# cn0383.net
KiCad netlist of a schematic drawn in Altium Designer
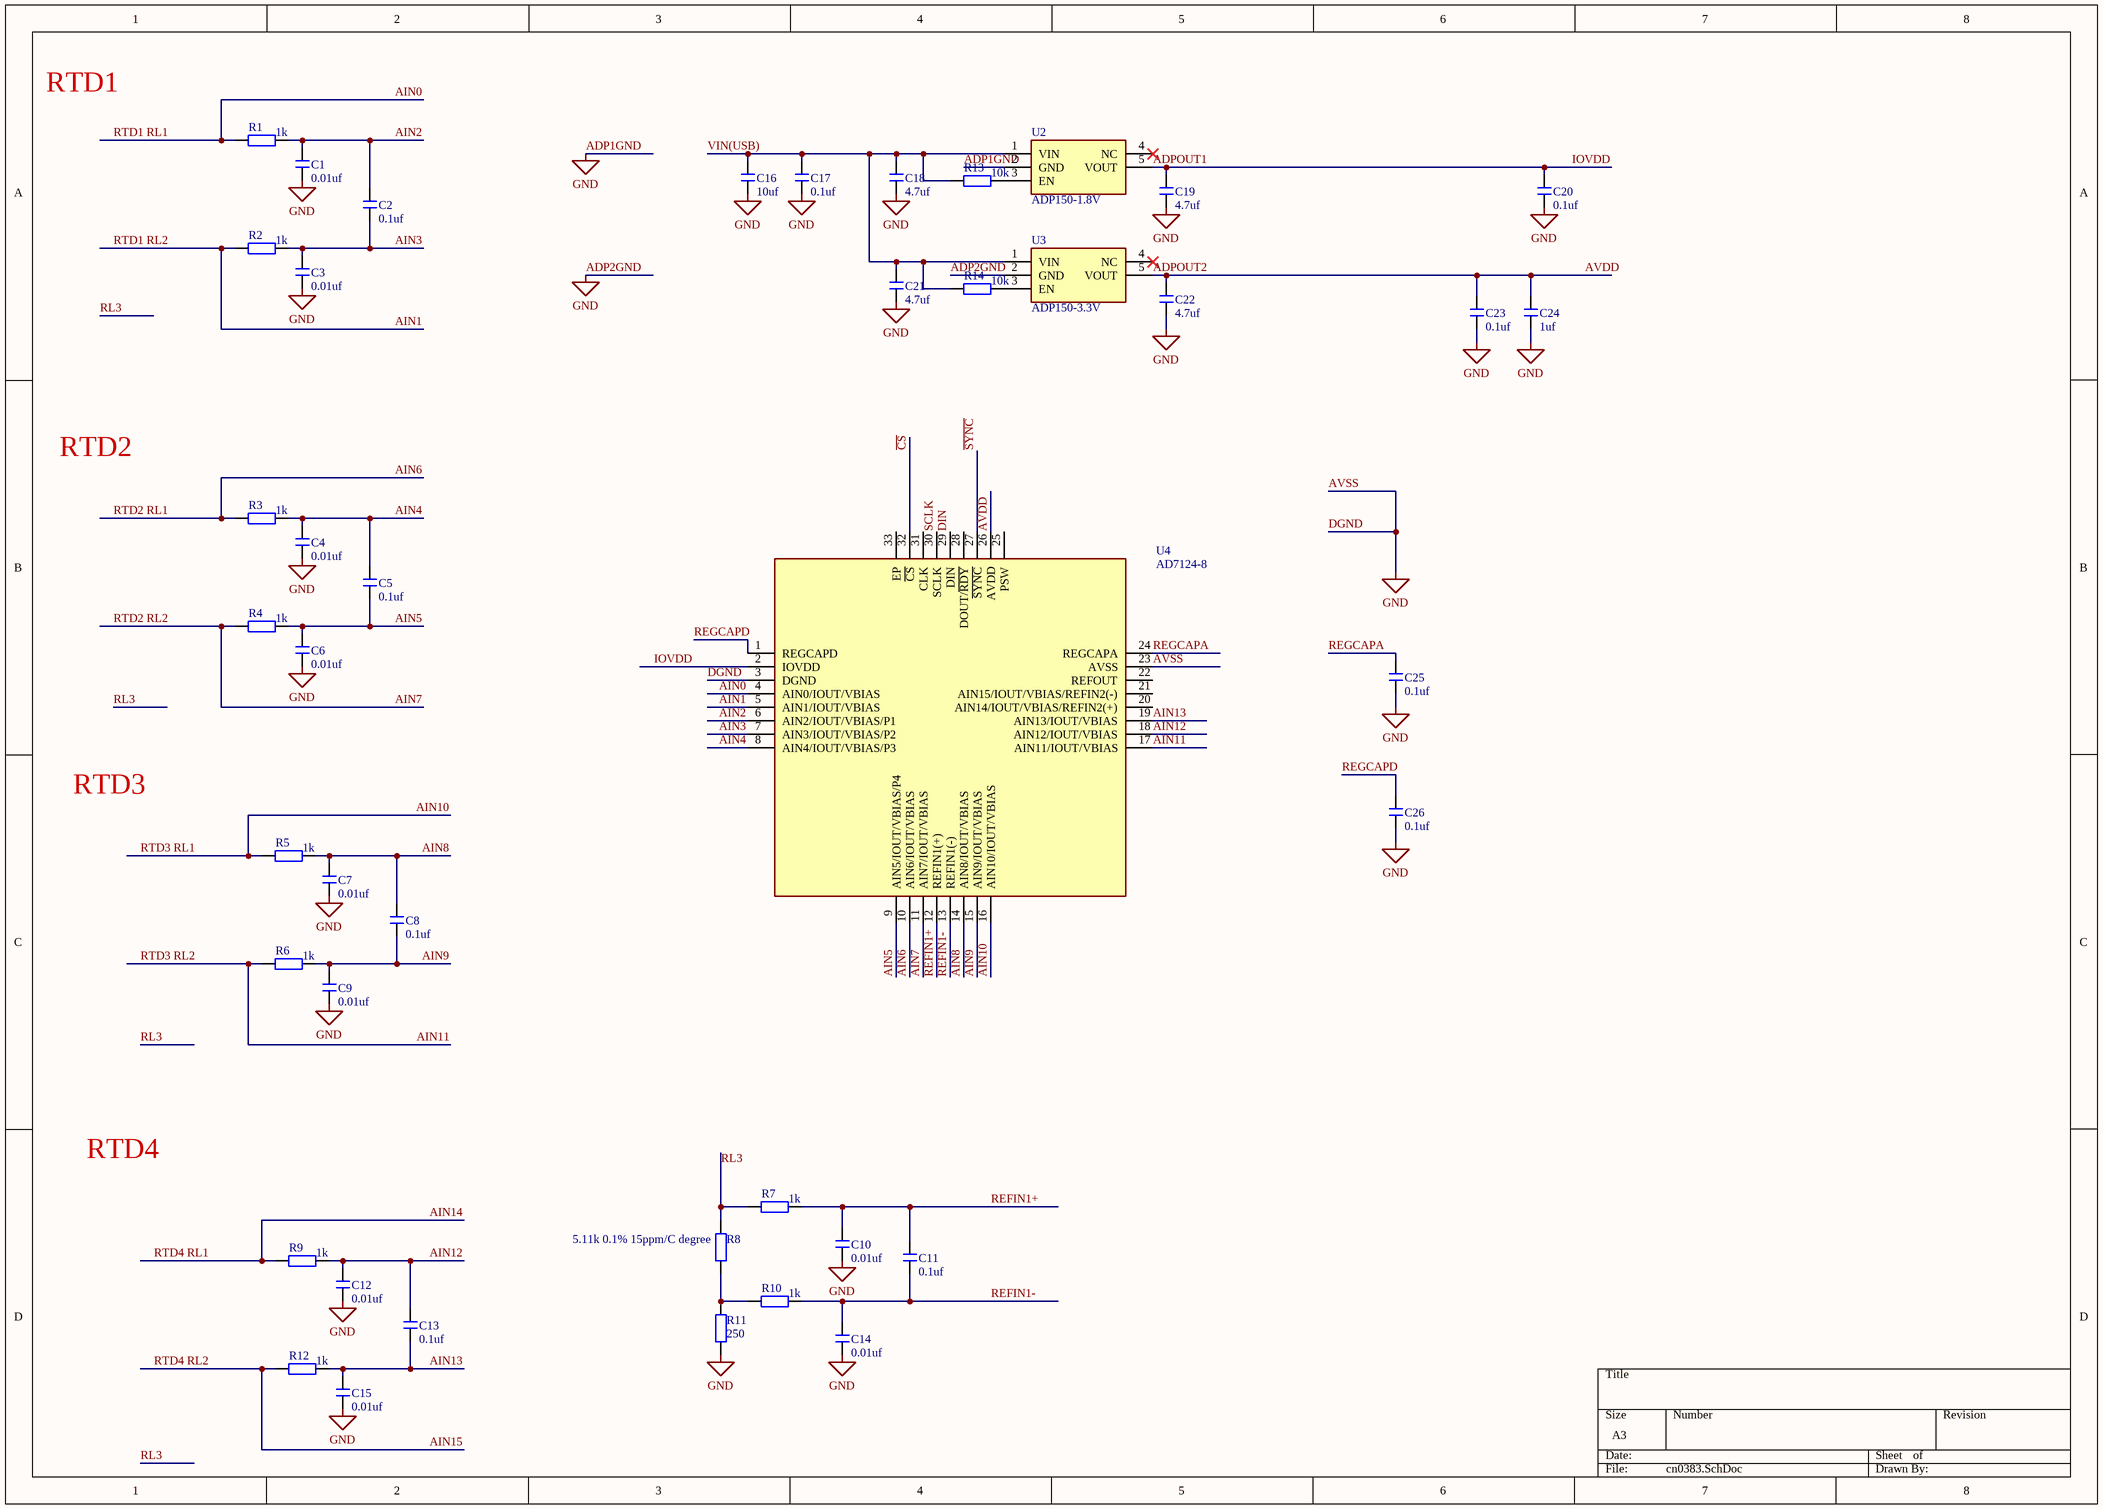
[diagram p0: cn0383.SchDoc]

(export (version "E")
  (design (tool "Eeschema 10.0.6"))
  (components
    (comp (ref "C1")
      (value "0.01uf")
      (footprint "C 0805_L")
      (description "贴片电容")
      (libsource (lib "0.1 - 电阻-电容-电感") (part "C"))
    )
    (comp (ref "C2")
      (value "0.1uf")
      (footprint "C 0805_L")
      (description "贴片电容")
      (libsource (lib "0.1 - 电阻-电容-电感") (part "C"))
    )
    (comp (ref "C3")
      (value "0.01uf")
      (footprint "C 0805_L")
      (description "贴片电容")
      (libsource (lib "0.1 - 电阻-电容-电感") (part "C"))
    )
    (comp (ref "C4")
      (value "0.01uf")
      (footprint "C 0805_L")
      (description "贴片电容")
      (libsource (lib "0.1 - 电阻-电容-电感") (part "C"))
    )
    (comp (ref "C5")
      (value "0.1uf")
      (footprint "C 0805_L")
      (description "贴片电容")
      (libsource (lib "0.1 - 电阻-电容-电感") (part "C"))
    )
    (comp (ref "C6")
      (value "0.01uf")
      (footprint "C 0805_L")
      (description "贴片电容")
      (libsource (lib "0.1 - 电阻-电容-电感") (part "C"))
    )
    (comp (ref "C7")
      (value "0.01uf")
      (footprint "C 0805_L")
      (description "贴片电容")
      (libsource (lib "0.1 - 电阻-电容-电感") (part "C"))
    )
    (comp (ref "C8")
      (value "0.1uf")
      (footprint "C 0805_L")
      (description "贴片电容")
      (libsource (lib "0.1 - 电阻-电容-电感") (part "C"))
    )
    (comp (ref "C9")
      (value "0.01uf")
      (footprint "C 0805_L")
      (description "贴片电容")
      (libsource (lib "0.1 - 电阻-电容-电感") (part "C"))
    )
    (comp (ref "C10")
      (value "0.01uf")
      (footprint "C 0805_L")
      (description "贴片电容")
      (libsource (lib "0.1 - 电阻-电容-电感") (part "C"))
    )
    (comp (ref "C11")
      (value "0.1uf")
      (footprint "C 0805_L")
      (description "贴片电容")
      (libsource (lib "0.1 - 电阻-电容-电感") (part "C"))
    )
    (comp (ref "C12")
      (value "0.01uf")
      (footprint "C 0805_L")
      (description "贴片电容")
      (libsource (lib "0.1 - 电阻-电容-电感") (part "C"))
    )
    (comp (ref "C13")
      (value "0.1uf")
      (footprint "C 0805_L")
      (description "贴片电容")
      (libsource (lib "0.1 - 电阻-电容-电感") (part "C"))
    )
    (comp (ref "C14")
      (value "0.01uf")
      (footprint "C 0805_L")
      (description "贴片电容")
      (libsource (lib "0.1 - 电阻-电容-电感") (part "C"))
    )
    (comp (ref "C15")
      (value "0.01uf")
      (footprint "C 0805_L")
      (description "贴片电容")
      (libsource (lib "0.1 - 电阻-电容-电感") (part "C"))
    )
    (comp (ref "C16")
      (value "10uf")
      (footprint "C 0805_L")
      (description "贴片电容")
      (libsource (lib "0.1 - 电阻-电容-电感") (part "C"))
    )
    (comp (ref "C17")
      (value "0.1uf")
      (footprint "C 0805_L")
      (description "贴片电容")
      (libsource (lib "0.1 - 电阻-电容-电感") (part "C"))
    )
    (comp (ref "C18")
      (value "4.7uf")
      (footprint "C 0805_L")
      (description "贴片电容")
      (libsource (lib "0.1 - 电阻-电容-电感") (part "C"))
    )
    (comp (ref "C19")
      (value "4.7uf")
      (footprint "C 0805_L")
      (description "贴片电容")
      (libsource (lib "0.1 - 电阻-电容-电感") (part "C"))
    )
    (comp (ref "C20")
      (value "0.1uf")
      (footprint "C 0805_L")
      (description "贴片电容")
      (libsource (lib "0.1 - 电阻-电容-电感") (part "C"))
    )
    (comp (ref "C21")
      (value "4.7uf")
      (footprint "C 0805_L")
      (description "贴片电容")
      (libsource (lib "0.1 - 电阻-电容-电感") (part "C"))
    )
    (comp (ref "C22")
      (value "4.7uf")
      (footprint "C 0805_L")
      (description "贴片电容")
      (libsource (lib "0.1 - 电阻-电容-电感") (part "C"))
    )
    (comp (ref "C23")
      (value "0.1uf")
      (footprint "C 0805_L")
      (description "贴片电容")
      (libsource (lib "0.1 - 电阻-电容-电感") (part "C"))
    )
    (comp (ref "C24")
      (value "1uf")
      (footprint "C 0805_L")
      (description "贴片电容")
      (libsource (lib "0.1 - 电阻-电容-电感") (part "C"))
    )
    (comp (ref "C25")
      (value "0.1uf")
      (footprint "C 0805_L")
      (description "贴片电容")
      (libsource (lib "0.1 - 电阻-电容-电感") (part "C"))
    )
    (comp (ref "C26")
      (value "0.1uf")
      (footprint "C 0805_L")
      (description "贴片电容")
      (libsource (lib "0.1 - 电阻-电容-电感") (part "C"))
    )
    (comp (ref "R1")
      (value "1k")
      (footprint "0805_R")
      (description "贴片电阻 0805 电阻")
      (libsource (lib "") (part "0805 电阻_1"))
    )
    (comp (ref "R2")
      (value "1k")
      (footprint "0805_R")
      (description "贴片电阻 0805 电阻")
      (libsource (lib "") (part "0805 电阻_1"))
    )
    (comp (ref "R3")
      (value "1k")
      (footprint "0805_R")
      (description "贴片电阻 0805 电阻")
      (libsource (lib "") (part "0805 电阻_1"))
    )
    (comp (ref "R4")
      (value "1k")
      (footprint "0805_R")
      (description "贴片电阻 0805 电阻")
      (libsource (lib "") (part "0805 电阻_1"))
    )
    (comp (ref "R5")
      (value "1k")
      (footprint "0805_R")
      (description "贴片电阻 0805 电阻")
      (libsource (lib "") (part "0805 电阻_1"))
    )
    (comp (ref "R6")
      (value "1k")
      (footprint "0805_R")
      (description "贴片电阻 0805 电阻")
      (libsource (lib "") (part "0805 电阻_1"))
    )
    (comp (ref "R7")
      (value "1k")
      (footprint "0805_R")
      (description "贴片电阻 0805 电阻")
      (libsource (lib "") (part "0805 电阻_1"))
    )
    (comp (ref "R8")
      (value "5.11k 0.1% 15ppm/C degree")
      (footprint "0805_R")
      (description "贴片电阻 0805 电阻")
      (libsource (lib "逍遥封装库") (part "0805 电阻"))
    )
    (comp (ref "R9")
      (value "1k")
      (footprint "0805_R")
      (description "贴片电阻 0805 电阻")
      (libsource (lib "") (part "0805 电阻_1"))
    )
    (comp (ref "R10")
      (value "1k")
      (footprint "0805_R")
      (description "贴片电阻 0805 电阻")
      (libsource (lib "") (part "0805 电阻_1"))
    )
    (comp (ref "R11")
      (value "250")
      (footprint "0805_R")
      (description "Reference buffer Headroom 贴片电阻 0805 电阻")
      (libsource (lib "逍遥封装库") (part "0805 电阻"))
    )
    (comp (ref "R12")
      (value "1k")
      (footprint "0805_R")
      (description "贴片电阻 0805 电阻")
      (libsource (lib "") (part "0805 电阻_1"))
    )
    (comp (ref "R13")
      (value "10k")
      (footprint "0805_R")
      (description "贴片电阻 0805 电阻")
      (libsource (lib "") (part "0805 电阻_1"))
    )
    (comp (ref "R14")
      (value "10k")
      (footprint "0805_R")
      (description "贴片电阻 0805 电阻")
      (libsource (lib "") (part "0805 电阻_1"))
    )
    (comp (ref "U2")
      (value "ADP150-1.8V")
      (description "IOVDD needs 1.8V")
      (libsource (lib "CN0383") (part "ADP150"))
    )
    (comp (ref "U3")
      (value "ADP150-3.3V")
      (description "ACDD needs 3.3V")
      (libsource (lib "CN0383") (part "ADP150"))
    )
    (comp (ref "U4") (value "AD7124-8") (libsource (lib "CN0383") (part "AD7124-8")))
  )
  (nets
    (net (code "1") (name "/ADPOUT1") (class "Default")
      (node (ref "C19") (pin "2") (pinfunction "2_2") (pintype "passive"))
      (node (ref "C20") (pin "2") (pinfunction "2_2") (pintype "passive"))
      (node (ref "U2") (pin "5") (pinfunction "VOUT_5") (pintype "passive"))
      (node (ref "U4") (pin "2") (pinfunction "IOVDD_2") (pintype "passive"))
    )
    (net (code "2") (name "/ADPOUT2") (class "Default")
      (node (ref "C22") (pin "2") (pinfunction "2_2") (pintype "passive"))
      (node (ref "C23") (pin "2") (pinfunction "2_2") (pintype "passive"))
      (node (ref "C24") (pin "2") (pinfunction "2_2") (pintype "passive"))
      (node (ref "U3") (pin "5") (pinfunction "VOUT_5") (pintype "passive"))
      (node (ref "U4") (pin "26") (pinfunction "AVDD_26") (pintype "passive"))
    )
    (net (code "3") (name "/AIN0") (class "Default")
      (node (ref "R1") (pin "1") (pinfunction "1_1") (pintype "passive"))
      (node (ref "U4") (pin "4") (pinfunction "AIN0/IOUT/VBIAS_4") (pintype "passive"))
    )
    (net (code "4") (name "/AIN1") (class "Default")
      (node (ref "R2") (pin "1") (pinfunction "1_1") (pintype "passive"))
      (node (ref "U4") (pin "5") (pinfunction "AIN1/IOUT/VBIAS_5") (pintype "passive"))
    )
    (net (code "5") (name "/AIN2") (class "Default")
      (node (ref "C1") (pin "2") (pinfunction "2_2") (pintype "passive"))
      (node (ref "C2") (pin "2") (pinfunction "2_2") (pintype "passive"))
      (node (ref "R1") (pin "2") (pinfunction "2_2") (pintype "passive"))
      (node (ref "U4") (pin "6") (pinfunction "AIN2/IOUT/VBIAS/P1_6") (pintype "passive"))
    )
    (net (code "6") (name "/AIN3") (class "Default")
      (node (ref "C2") (pin "1") (pinfunction "1_1") (pintype "passive"))
      (node (ref "C3") (pin "2") (pinfunction "2_2") (pintype "passive"))
      (node (ref "R2") (pin "2") (pinfunction "2_2") (pintype "passive"))
      (node (ref "U4") (pin "7") (pinfunction "AIN3/IOUT/VBIAS/P2_7") (pintype "passive"))
    )
    (net (code "7") (name "/AIN4") (class "Default")
      (node (ref "C4") (pin "2") (pinfunction "2_2") (pintype "passive"))
      (node (ref "C5") (pin "2") (pinfunction "2_2") (pintype "passive"))
      (node (ref "R3") (pin "2") (pinfunction "2_2") (pintype "passive"))
      (node (ref "U4") (pin "8") (pinfunction "AIN4/IOUT/VBIAS/P3_8") (pintype "passive"))
    )
    (net (code "8") (name "/AIN5") (class "Default")
      (node (ref "C5") (pin "1") (pinfunction "1_1") (pintype "passive"))
      (node (ref "C6") (pin "2") (pinfunction "2_2") (pintype "passive"))
      (node (ref "R4") (pin "2") (pinfunction "2_2") (pintype "passive"))
      (node (ref "U4") (pin "9") (pinfunction "AIN5/IOUT/VBIAS/P4_9") (pintype "passive"))
    )
    (net (code "9") (name "/AIN6") (class "Default")
      (node (ref "R3") (pin "1") (pinfunction "1_1") (pintype "passive"))
      (node (ref "U4") (pin "10") (pinfunction "AIN6/IOUT/VBIAS_10") (pintype "passive"))
    )
    (net (code "10") (name "/AIN7") (class "Default")
      (node (ref "R4") (pin "1") (pinfunction "1_1") (pintype "passive"))
      (node (ref "U4") (pin "11") (pinfunction "AIN7/IOUT/VBIAS_11") (pintype "passive"))
    )
    (net (code "11") (name "/AIN8") (class "Default")
      (node (ref "C7") (pin "2") (pinfunction "2_2") (pintype "passive"))
      (node (ref "C8") (pin "2") (pinfunction "2_2") (pintype "passive"))
      (node (ref "R5") (pin "2") (pinfunction "2_2") (pintype "passive"))
      (node (ref "U4") (pin "14") (pinfunction "AIN8/IOUT/VBIAS_14") (pintype "passive"))
    )
    (net (code "12") (name "/AIN9") (class "Default")
      (node (ref "C8") (pin "1") (pinfunction "1_1") (pintype "passive"))
      (node (ref "C9") (pin "2") (pinfunction "2_2") (pintype "passive"))
      (node (ref "R6") (pin "2") (pinfunction "2_2") (pintype "passive"))
      (node (ref "U4") (pin "15") (pinfunction "AIN9/IOUT/VBIAS_15") (pintype "passive"))
    )
    (net (code "13") (name "/AIN10") (class "Default")
      (node (ref "R5") (pin "1") (pinfunction "1_1") (pintype "passive"))
      (node (ref "U4") (pin "16") (pinfunction "AIN10/IOUT/VBIAS_16") (pintype "passive"))
    )
    (net (code "14") (name "/AIN11") (class "Default")
      (node (ref "R6") (pin "1") (pinfunction "1_1") (pintype "passive"))
      (node (ref "U4") (pin "17") (pinfunction "AIN11/IOUT/VBIAS_17") (pintype "passive"))
    )
    (net (code "15") (name "/AIN12") (class "Default")
      (node (ref "C12") (pin "2") (pinfunction "2_2") (pintype "passive"))
      (node (ref "C13") (pin "2") (pinfunction "2_2") (pintype "passive"))
      (node (ref "R9") (pin "2") (pinfunction "2_2") (pintype "passive"))
      (node (ref "U4") (pin "18") (pinfunction "AIN12/IOUT/VBIAS_18") (pintype "passive"))
    )
    (net (code "16") (name "/AIN13") (class "Default")
      (node (ref "C13") (pin "1") (pinfunction "1_1") (pintype "passive"))
      (node (ref "C15") (pin "2") (pinfunction "2_2") (pintype "passive"))
      (node (ref "R12") (pin "2") (pinfunction "2_2") (pintype "passive"))
      (node (ref "U4") (pin "19") (pinfunction "AIN13/IOUT/VBIAS_19") (pintype "passive"))
    )
    (net (code "17") (name "/AIN14") (class "Default")
      (node (ref "R9") (pin "1") (pinfunction "1_1") (pintype "passive"))
    )
    (net (code "18") (name "/AIN15") (class "Default")
      (node (ref "R12") (pin "1") (pinfunction "1_1") (pintype "passive"))
    )
    (net (code "19") (name "/DIN") (class "Default")
      (node (ref "U4") (pin "29") (pinfunction "DIN_29") (pintype "passive"))
    )
    (net (code "20") (name "/REFIN1+") (class "Default")
      (node (ref "C10") (pin "2") (pinfunction "2_2") (pintype "passive"))
      (node (ref "C11") (pin "2") (pinfunction "2_2") (pintype "passive"))
      (node (ref "R7") (pin "2") (pinfunction "2_2") (pintype "passive"))
      (node (ref "U4") (pin "12") (pinfunction "REFIN1(+)_12") (pintype "passive"))
    )
    (net (code "21") (name "/REFIN1-") (class "Default")
      (node (ref "C11") (pin "1") (pinfunction "1_1") (pintype "passive"))
      (node (ref "C14") (pin "2") (pinfunction "2_2") (pintype "passive"))
      (node (ref "R10") (pin "2") (pinfunction "2_2") (pintype "passive"))
      (node (ref "U4") (pin "13") (pinfunction "REFIN1(-)_13") (pintype "passive"))
    )
    (net (code "22") (name "/REGCAPA") (class "Default")
      (node (ref "C25") (pin "2") (pinfunction "2_2") (pintype "passive"))
      (node (ref "U4") (pin "24") (pinfunction "REGCAPA_24") (pintype "passive"))
    )
    (net (code "23") (name "/REGCAPD") (class "Default")
      (node (ref "C26") (pin "2") (pinfunction "2_2") (pintype "passive"))
      (node (ref "U4") (pin "1") (pinfunction "REGCAPD_1") (pintype "passive"))
    )
    (net (code "24") (name "/RL3") (class "Default")
      (node (ref "R7") (pin "1") (pinfunction "1_1") (pintype "passive"))
      (node (ref "R8") (pin "2") (pinfunction "2_2") (pintype "passive"))
    )
    (net (code "25") (name "/SCLK") (class "Default")
      (node (ref "U4") (pin "30") (pinfunction "SCLK_30") (pintype "passive"))
    )
    (net (code "26") (name "/VIN(USB)") (class "Default")
      (node (ref "C16") (pin "2") (pinfunction "2_2") (pintype "passive"))
      (node (ref "C17") (pin "2") (pinfunction "2_2") (pintype "passive"))
      (node (ref "C18") (pin "2") (pinfunction "2_2") (pintype "passive"))
      (node (ref "C21") (pin "2") (pinfunction "2_2") (pintype "passive"))
      (node (ref "R13") (pin "1") (pinfunction "1_1") (pintype "passive"))
      (node (ref "R14") (pin "1") (pinfunction "1_1") (pintype "passive"))
      (node (ref "U2") (pin "1") (pinfunction "VIN_1") (pintype "passive"))
      (node (ref "U3") (pin "1") (pinfunction "VIN_1") (pintype "passive"))
    )
    (net (code "27") (name "/~{CS}") (class "Default")
      (node (ref "U4") (pin "32") (pinfunction "~{CS}_32") (pintype "passive"))
    )
    (net (code "28") (name "/~{SYNC}") (class "Default")
      (node (ref "U4") (pin "27") (pinfunction "~{SYNC}_27") (pintype "passive"))
    )
    (net (code "29") (name "GND") (class "Default")
      (node (ref "C1") (pin "1") (pinfunction "1_1") (pintype "passive"))
      (node (ref "C10") (pin "1") (pinfunction "1_1") (pintype "passive"))
      (node (ref "C12") (pin "1") (pinfunction "1_1") (pintype "passive"))
      (node (ref "C14") (pin "1") (pinfunction "1_1") (pintype "passive"))
      (node (ref "C15") (pin "1") (pinfunction "1_1") (pintype "passive"))
      (node (ref "C16") (pin "1") (pinfunction "1_1") (pintype "passive"))
      (node (ref "C17") (pin "1") (pinfunction "1_1") (pintype "passive"))
      (node (ref "C18") (pin "1") (pinfunction "1_1") (pintype "passive"))
      (node (ref "C19") (pin "1") (pinfunction "1_1") (pintype "passive"))
      (node (ref "C20") (pin "1") (pinfunction "1_1") (pintype "passive"))
      (node (ref "C21") (pin "1") (pinfunction "1_1") (pintype "passive"))
      (node (ref "C22") (pin "1") (pinfunction "1_1") (pintype "passive"))
      (node (ref "C23") (pin "1") (pinfunction "1_1") (pintype "passive"))
      (node (ref "C24") (pin "1") (pinfunction "1_1") (pintype "passive"))
      (node (ref "C25") (pin "1") (pinfunction "1_1") (pintype "passive"))
      (node (ref "C26") (pin "1") (pinfunction "1_1") (pintype "passive"))
      (node (ref "C3") (pin "1") (pinfunction "1_1") (pintype "passive"))
      (node (ref "C4") (pin "1") (pinfunction "1_1") (pintype "passive"))
      (node (ref "C6") (pin "1") (pinfunction "1_1") (pintype "passive"))
      (node (ref "C7") (pin "1") (pinfunction "1_1") (pintype "passive"))
      (node (ref "C9") (pin "1") (pinfunction "1_1") (pintype "passive"))
      (node (ref "R11") (pin "1") (pinfunction "1_1") (pintype "passive"))
      (node (ref "U2") (pin "2") (pinfunction "GND_2") (pintype "passive"))
      (node (ref "U3") (pin "2") (pinfunction "GND_2") (pintype "passive"))
      (node (ref "U4") (pin "23") (pinfunction "AVSS_23") (pintype "passive"))
      (node (ref "U4") (pin "3") (pinfunction "DGND_3") (pintype "passive"))
    )
    (net (code "30") (name "Net-(R10-Pad1)") (class "Default")
      (node (ref "R10") (pin "1") (pinfunction "1_1") (pintype "passive"))
      (node (ref "R11") (pin "2") (pinfunction "2_2") (pintype "passive"))
      (node (ref "R8") (pin "1") (pinfunction "1_1") (pintype "passive"))
    )
    (net (code "31") (name "Net-(U2-EN)") (class "Default")
      (node (ref "R13") (pin "2") (pinfunction "2_2") (pintype "passive"))
      (node (ref "U2") (pin "3") (pinfunction "EN_3") (pintype "passive"))
    )
    (net (code "32") (name "Net-(U3-EN)") (class "Default")
      (node (ref "R14") (pin "2") (pinfunction "2_2") (pintype "passive"))
      (node (ref "U3") (pin "3") (pinfunction "EN_3") (pintype "passive"))
    )
    (net (code "33") (name "unconnected-(U2-NC-Pad4)") (class "Default")
      (node (ref "U2") (pin "4") (pinfunction "NC_4") (pintype "passive+no_connect"))
    )
    (net (code "34") (name "unconnected-(U3-NC-Pad4)") (class "Default")
      (node (ref "U3") (pin "4") (pinfunction "NC_4") (pintype "passive+no_connect"))
    )
    (net (code "35") (name "unconnected-(U4-AIN14{slash}IOUT{slash}VBIAS{slash}REFIN2(+)-Pad20)") (class "Default")
      (node (ref "U4") (pin "20") (pinfunction "AIN14/IOUT/VBIAS/REFIN2(+)_20") (pintype "passive"))
    )
    (net (code "36") (name "unconnected-(U4-AIN15{slash}IOUT{slash}VBIAS{slash}REFIN2(-)-Pad21)") (class "Default")
      (node (ref "U4") (pin "21") (pinfunction "AIN15/IOUT/VBIAS/REFIN2(-)_21") (pintype "passive"))
    )
    (net (code "37") (name "unconnected-(U4-CLK-Pad31)") (class "Default")
      (node (ref "U4") (pin "31") (pinfunction "CLK_31") (pintype "passive"))
    )
    (net (code "38") (name "unconnected-(U4-DOUT{slash}~{RDY}-Pad28)") (class "Default")
      (node (ref "U4") (pin "28") (pinfunction "DOUT/~{RDY}_28") (pintype "passive"))
    )
    (net (code "39") (name "unconnected-(U4-EP-Pad33)") (class "Default")
      (node (ref "U4") (pin "33") (pinfunction "EP_33") (pintype "passive"))
    )
    (net (code "40") (name "unconnected-(U4-PSW-Pad25)") (class "Default")
      (node (ref "U4") (pin "25") (pinfunction "PSW_25") (pintype "passive"))
    )
    (net (code "41") (name "unconnected-(U4-REFOUT-Pad22)") (class "Default")
      (node (ref "U4") (pin "22") (pinfunction "REFOUT_22") (pintype "passive"))
    )
  )
)
